# Microphone.net
KiCad netlist of a schematic drawn in Altium Designer
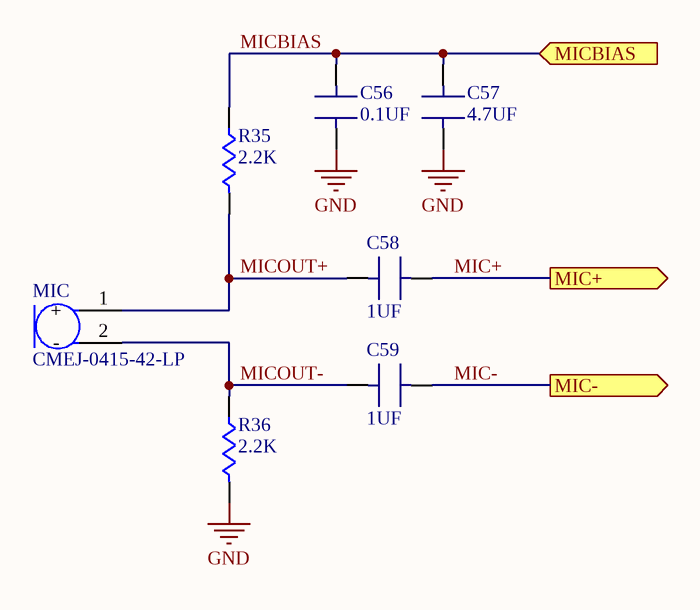
[diagram p0: Microphone.SchDoc]

(export (version "E")
  (design (tool "Eeschema 10.0.6"))
  (components
    (comp (ref "C56")
      (value "0.1UF")
      (footprint "CAP: 0603")
      (description "CAP SMD 0603")
      (libsource (lib "HZSchLib") (part "CAP 0603"))
    )
    (comp (ref "C57")
      (value "4.7UF")
      (footprint "CAP: 0805")
      (description "CAP SMD 0805")
      (libsource (lib "HZSchLib") (part "CAP 0805"))
    )
    (comp (ref "C58")
      (value "1UF")
      (footprint "CAP: 0603")
      (description "CAP SMD 0603")
      (libsource (lib "HZSchLib") (part "CAP 0603"))
    )
    (comp (ref "C59")
      (value "1UF")
      (footprint "CAP: 0603")
      (description "CAP SMD 0603")
      (libsource (lib "HZSchLib") (part "CAP 0603"))
    )
    (comp (ref "MIC")
      (value "CMEJ-0415-42-LP")
      (footprint "CMEJ041542LP")
      (description "4.0 mm, Omnidirectional, PCB Mount, 2.0 Vdc, Elecret Condenser Microphone")
      (fields (field (name "MANUFACTURER") "CUI Devices"))
      (libsource (lib "HZSchLib") (part "CMEJ-0415-42-LP"))
    )
    (comp (ref "R35")
      (value "2.2K")
      (footprint "RES: 0603")
      (description "RES SMD 0603")
      (libsource (lib "HZSchLib") (part "RES 0603"))
    )
    (comp (ref "R36")
      (value "2.2K")
      (footprint "RES: 0603")
      (description "RES SMD 0603")
      (libsource (lib "HZSchLib") (part "RES 0603"))
    )
  )
  (nets
    (net (code "1") (name "/MIC+") (class "Default")
      (node (ref "C58") (pin "2") (pinfunction "B_2") (pintype "passive"))
    )
    (net (code "2") (name "/MIC-") (class "Default")
      (node (ref "C59") (pin "2") (pinfunction "B_2") (pintype "passive"))
    )
    (net (code "3") (name "/MICBIAS") (class "Default")
      (node (ref "C56") (pin "1") (pinfunction "A_1") (pintype "passive"))
      (node (ref "C57") (pin "2") (pinfunction "B_2") (pintype "passive"))
      (node (ref "R35") (pin "2") (pinfunction "2_2") (pintype "passive"))
    )
    (net (code "4") (name "/MICOUT+") (class "Default")
      (node (ref "C58") (pin "1") (pinfunction "A_1") (pintype "passive"))
      (node (ref "MIC") (pin "1") (pinfunction "+_1") (pintype "passive"))
      (node (ref "R35") (pin "1") (pinfunction "1_1") (pintype "passive"))
    )
    (net (code "5") (name "/MICOUT-") (class "Default")
      (node (ref "C59") (pin "1") (pinfunction "A_1") (pintype "passive"))
      (node (ref "MIC") (pin "2") (pinfunction "-_2") (pintype "passive"))
      (node (ref "R36") (pin "2") (pinfunction "2_2") (pintype "passive"))
    )
    (net (code "6") (name "GND") (class "Default")
      (node (ref "C56") (pin "2") (pinfunction "B_2") (pintype "passive"))
      (node (ref "C57") (pin "1") (pinfunction "A_1") (pintype "passive"))
      (node (ref "R36") (pin "1") (pinfunction "1_1") (pintype "passive"))
    )
  )
)
